# ESP32_TRIGGER_AUDIO_SCHEMATIC.net
KiCad netlist of a schematic drawn in Altium Designer
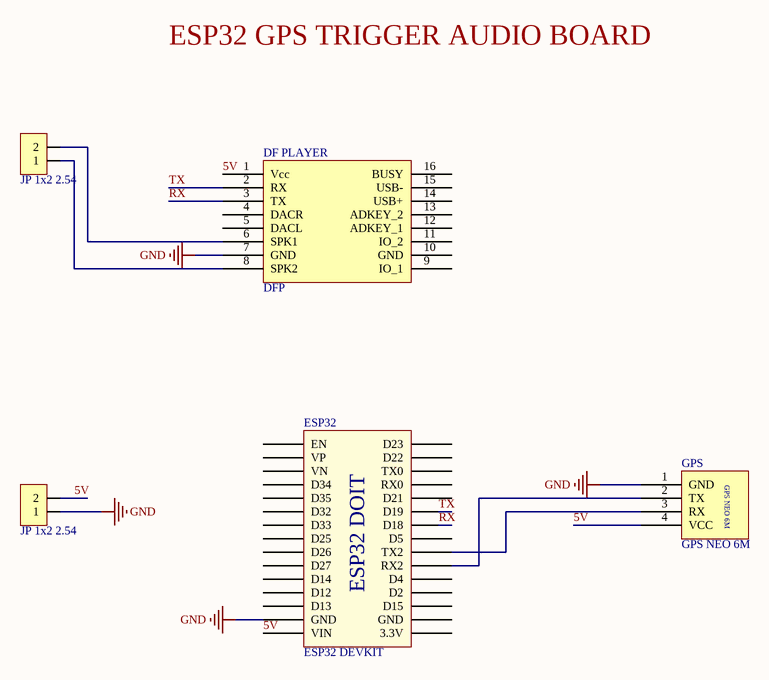
[diagram p0: ESP32_TRIGGER_AUDIO_SCHEMATIC.SchDoc]

(export (version "E")
  (design (tool "Eeschema 10.0.6"))
  (components
    (comp (ref "DF PLAYER")
      (value "DFP")
      (footprint "DFPlayer")
      (description "DFPlayer")
      (libsource (lib "Schlib") (part "DFPlayer"))
    )
    (comp (ref "ESP32")
      (value "ESP32 DEVKIT")
      (footprint "ESP32 WROOM 32 KIT - duplicate")
      (libsource (lib "Schlib") (part "ESP32 WROOM 32 KIT"))
    )
    (comp (ref "GPS")
      (value "GPS NEO 6M")
      (footprint "GPS NEO 6M")
      (libsource (lib "Schlib") (part "GPS NEO 6M"))
    )
    (comp (ref "JP1")
      (value "JP 1x2 2.54")
      (footprint "JP 1x2 DT")
      (description "Cắm")
      (libsource (lib "Schlib") (part "JP 1x2 2.54 Duc Thang"))
    )
    (comp (ref "JP2")
      (value "JP 1x2 2.54")
      (footprint "JP 1x2 DT")
      (description "Cắm")
      (libsource (lib "Schlib") (part "JP 1x2 2.54 Duc Thang"))
    )
  )
  (nets
    (net (code "1") (name "/5V") (class "Default")
      (node (ref "DF PLAYER") (pin "1") (pinfunction "Vcc_1") (pintype "passive"))
      (node (ref "ESP32") (pin "15") (pinfunction "VIN_15") (pintype "passive"))
      (node (ref "GPS") (pin "4") (pinfunction "VCC_4") (pintype "passive"))
      (node (ref "JP1") (pin "2") (pinfunction "2_2") (pintype "passive"))
    )
    (net (code "2") (name "/RX") (class "Default")
      (node (ref "DF PLAYER") (pin "3") (pinfunction "TX_3") (pintype "passive"))
      (node (ref "ESP32") (pin "24") (pinfunction "D18_24") (pintype "passive"))
    )
    (net (code "3") (name "/TX") (class "Default")
      (node (ref "DF PLAYER") (pin "2") (pinfunction "RX_2") (pintype "passive"))
      (node (ref "ESP32") (pin "25") (pinfunction "D19_25") (pintype "passive"))
    )
    (net (code "4") (name "GND") (class "Default")
      (node (ref "DF PLAYER") (pin "7") (pinfunction "GND_7") (pintype "passive"))
      (node (ref "ESP32") (pin "14") (pinfunction "GND_14") (pintype "passive"))
      (node (ref "GPS") (pin "1") (pinfunction "GND_1") (pintype "passive"))
      (node (ref "JP1") (pin "1") (pinfunction "1_1") (pintype "passive"))
    )
    (net (code "5") (name "Net-(DF PLAYER-SPK1)") (class "Default")
      (node (ref "DF PLAYER") (pin "6") (pinfunction "SPK1_6") (pintype "passive"))
      (node (ref "JP2") (pin "2") (pinfunction "2_2") (pintype "passive"))
    )
    (net (code "6") (name "Net-(DF PLAYER-SPK2)") (class "Default")
      (node (ref "DF PLAYER") (pin "8") (pinfunction "SPK2_8") (pintype "passive"))
      (node (ref "JP2") (pin "1") (pinfunction "1_1") (pintype "passive"))
    )
    (net (code "7") (name "Net-(ESP32-RX2)") (class "Default")
      (node (ref "ESP32") (pin "21") (pinfunction "RX2_21") (pintype "passive"))
      (node (ref "GPS") (pin "2") (pinfunction "TX_2") (pintype "passive"))
    )
    (net (code "8") (name "Net-(ESP32-TX2)") (class "Default")
      (node (ref "ESP32") (pin "22") (pinfunction "TX2_22") (pintype "passive"))
      (node (ref "GPS") (pin "3") (pinfunction "RX_3") (pintype "passive"))
    )
    (net (code "9") (name "unconnected-(DF PLAYER-ADKEY_1-Pad12)") (class "Default")
      (node (ref "DF PLAYER") (pin "12") (pinfunction "ADKEY_1_12") (pintype "passive"))
    )
    (net (code "10") (name "unconnected-(DF PLAYER-ADKEY_2-Pad13)") (class "Default")
      (node (ref "DF PLAYER") (pin "13") (pinfunction "ADKEY_2_13") (pintype "passive"))
    )
    (net (code "11") (name "unconnected-(DF PLAYER-BUSY-Pad16)") (class "Default")
      (node (ref "DF PLAYER") (pin "16") (pinfunction "BUSY_16") (pintype "passive"))
    )
    (net (code "12") (name "unconnected-(DF PLAYER-DACL-Pad5)") (class "Default")
      (node (ref "DF PLAYER") (pin "5") (pinfunction "DACL_5") (pintype "passive"))
    )
    (net (code "13") (name "unconnected-(DF PLAYER-DACR-Pad4)") (class "Default")
      (node (ref "DF PLAYER") (pin "4") (pinfunction "DACR_4") (pintype "passive"))
    )
    (net (code "14") (name "unconnected-(DF PLAYER-GND-Pad10)") (class "Default")
      (node (ref "DF PLAYER") (pin "10") (pinfunction "GND_10") (pintype "passive"))
    )
    (net (code "15") (name "unconnected-(DF PLAYER-IO_1-Pad9)") (class "Default")
      (node (ref "DF PLAYER") (pin "9") (pinfunction "IO_1_9") (pintype "passive"))
    )
    (net (code "16") (name "unconnected-(DF PLAYER-IO_2-Pad11)") (class "Default")
      (node (ref "DF PLAYER") (pin "11") (pinfunction "IO_2_11") (pintype "passive"))
    )
    (net (code "17") (name "unconnected-(DF PLAYER-USB+-Pad14)") (class "Default")
      (node (ref "DF PLAYER") (pin "14") (pinfunction "USB+_14") (pintype "passive"))
    )
    (net (code "18") (name "unconnected-(DF PLAYER-USB--Pad15)") (class "Default")
      (node (ref "DF PLAYER") (pin "15") (pinfunction "USB-_15") (pintype "passive"))
    )
    (net (code "19") (name "unconnected-(ESP32-3.3V-Pad16)") (class "Default")
      (node (ref "ESP32") (pin "16") (pinfunction "3.3V_16") (pintype "passive"))
    )
    (net (code "20") (name "unconnected-(ESP32-D2-Pad19)") (class "Default")
      (node (ref "ESP32") (pin "19") (pinfunction "D2_19") (pintype "passive"))
    )
    (net (code "21") (name "unconnected-(ESP32-D4-Pad20)") (class "Default")
      (node (ref "ESP32") (pin "20") (pinfunction "D4_20") (pintype "passive"))
    )
    (net (code "22") (name "unconnected-(ESP32-D5-Pad23)") (class "Default")
      (node (ref "ESP32") (pin "23") (pinfunction "D5_23") (pintype "passive"))
    )
    (net (code "23") (name "unconnected-(ESP32-D12-Pad12)") (class "Default")
      (node (ref "ESP32") (pin "12") (pinfunction "D12_12") (pintype "passive"))
    )
    (net (code "24") (name "unconnected-(ESP32-D13-Pad13)") (class "Default")
      (node (ref "ESP32") (pin "13") (pinfunction "D13_13") (pintype "passive"))
    )
    (net (code "25") (name "unconnected-(ESP32-D14-Pad11)") (class "Default")
      (node (ref "ESP32") (pin "11") (pinfunction "D14_11") (pintype "passive"))
    )
    (net (code "26") (name "unconnected-(ESP32-D15-Pad18)") (class "Default")
      (node (ref "ESP32") (pin "18") (pinfunction "D15_18") (pintype "passive"))
    )
    (net (code "27") (name "unconnected-(ESP32-D21-Pad26)") (class "Default")
      (node (ref "ESP32") (pin "26") (pinfunction "D21_26") (pintype "passive"))
    )
    (net (code "28") (name "unconnected-(ESP32-D22-Pad29)") (class "Default")
      (node (ref "ESP32") (pin "29") (pinfunction "D22_29") (pintype "passive"))
    )
    (net (code "29") (name "unconnected-(ESP32-D23-Pad30)") (class "Default")
      (node (ref "ESP32") (pin "30") (pinfunction "D23_30") (pintype "passive"))
    )
    (net (code "30") (name "unconnected-(ESP32-D25-Pad8)") (class "Default")
      (node (ref "ESP32") (pin "8") (pinfunction "D25_8") (pintype "passive"))
    )
    (net (code "31") (name "unconnected-(ESP32-D26-Pad9)") (class "Default")
      (node (ref "ESP32") (pin "9") (pinfunction "D26_9") (pintype "passive"))
    )
    (net (code "32") (name "unconnected-(ESP32-D27-Pad10)") (class "Default")
      (node (ref "ESP32") (pin "10") (pinfunction "D27_10") (pintype "passive"))
    )
    (net (code "33") (name "unconnected-(ESP32-D32-Pad6)") (class "Default")
      (node (ref "ESP32") (pin "6") (pinfunction "D32_6") (pintype "passive"))
    )
    (net (code "34") (name "unconnected-(ESP32-D33-Pad7)") (class "Default")
      (node (ref "ESP32") (pin "7") (pinfunction "D33_7") (pintype "passive"))
    )
    (net (code "35") (name "unconnected-(ESP32-D34-Pad4)") (class "Default")
      (node (ref "ESP32") (pin "4") (pinfunction "D34_4") (pintype "passive"))
    )
    (net (code "36") (name "unconnected-(ESP32-D35-Pad5)") (class "Default")
      (node (ref "ESP32") (pin "5") (pinfunction "D35_5") (pintype "passive"))
    )
    (net (code "37") (name "unconnected-(ESP32-EN-Pad1)") (class "Default")
      (node (ref "ESP32") (pin "1") (pinfunction "EN_1") (pintype "passive"))
    )
    (net (code "38") (name "unconnected-(ESP32-GND-Pad17)") (class "Default")
      (node (ref "ESP32") (pin "17") (pinfunction "GND_17") (pintype "passive"))
    )
    (net (code "39") (name "unconnected-(ESP32-RX0-Pad27)") (class "Default")
      (node (ref "ESP32") (pin "27") (pinfunction "RX0_27") (pintype "passive"))
    )
    (net (code "40") (name "unconnected-(ESP32-TX0-Pad28)") (class "Default")
      (node (ref "ESP32") (pin "28") (pinfunction "TX0_28") (pintype "passive"))
    )
    (net (code "41") (name "unconnected-(ESP32-VN-Pad3)") (class "Default")
      (node (ref "ESP32") (pin "3") (pinfunction "VN_3") (pintype "passive"))
    )
    (net (code "42") (name "unconnected-(ESP32-VP-Pad2)") (class "Default")
      (node (ref "ESP32") (pin "2") (pinfunction "VP_2") (pintype "passive"))
    )
  )
)
